# untitled.net
KiCad netlist of a schematic drawn in EAGLE
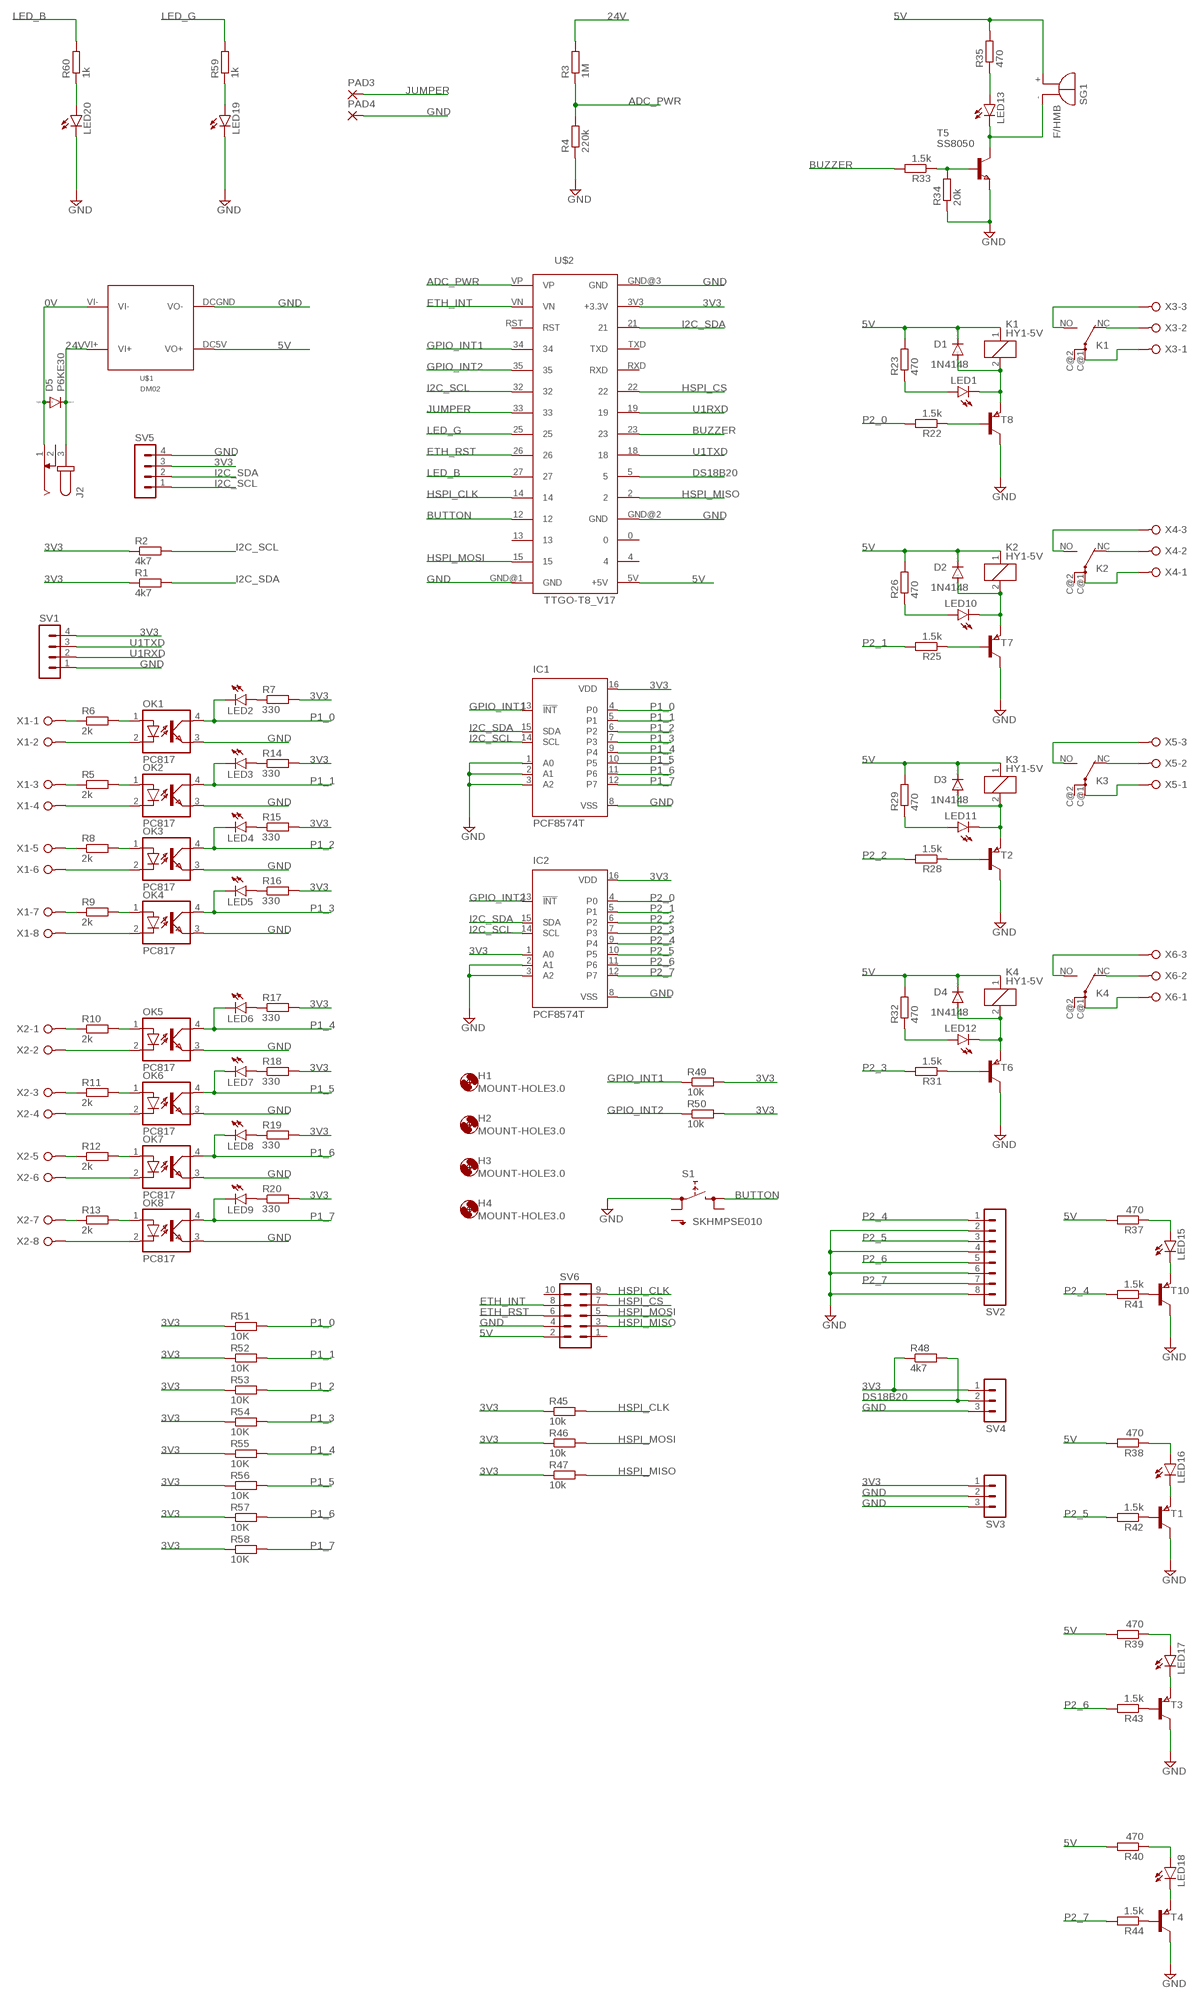
[diagram p0: schematic, sheet 1]

(export (version "E")
  (design (tool "Eeschema 10.0.6"))
  (components
    (comp (ref "D1")
      (value "1N4148")
      (footprint "eagle-import:SOD123")
      (libsource (lib "eagle-import") (part "diode_210_DIODE-SOD123"))
    )
    (comp (ref "D2")
      (value "1N4148")
      (footprint "eagle-import:SOD123")
      (libsource (lib "eagle-import") (part "diode_210_DIODE-SOD123"))
    )
    (comp (ref "D3")
      (value "1N4148")
      (footprint "eagle-import:SOD123")
      (libsource (lib "eagle-import") (part "diode_210_DIODE-SOD123"))
    )
    (comp (ref "D4")
      (value "1N4148")
      (footprint "eagle-import:SOD123")
      (libsource (lib "eagle-import") (part "diode_210_DIODE-SOD123"))
    )
    (comp (ref "D5")
      (value "P6KE30")
      (footprint "eagle-import:D-10")
      (libsource (lib "eagle-import") (part "DIODE-D-10"))
    )
    (comp (ref "H1")
      (value "MOUNT-HOLE3.0")
      (footprint "eagle-import:3,0")
      (libsource (lib "eagle-import") (part "MOUNT-HOLE3.0"))
    )
    (comp (ref "H2")
      (value "MOUNT-HOLE3.0")
      (footprint "eagle-import:3,0")
      (libsource (lib "eagle-import") (part "MOUNT-HOLE3.0"))
    )
    (comp (ref "H3")
      (value "MOUNT-HOLE3.0")
      (footprint "eagle-import:3,0")
      (libsource (lib "eagle-import") (part "MOUNT-HOLE3.0"))
    )
    (comp (ref "H4")
      (value "MOUNT-HOLE3.0")
      (footprint "eagle-import:3,0")
      (libsource (lib "eagle-import") (part "MOUNT-HOLE3.0"))
    )
    (comp (ref "IC1")
      (value "PCF8574T")
      (footprint "eagle-import:SO16W")
      (fields (field (name "MPN") "PCF8574T/3,512"))
      (libsource (lib "eagle-import") (part "PCF8574T"))
    )
    (comp (ref "IC2")
      (value "PCF8574T")
      (footprint "eagle-import:SO16W")
      (fields (field (name "MPN") "PCF8574T/3,512"))
      (libsource (lib "eagle-import") (part "PCF8574T"))
    )
    (comp (ref "J2")
      (value "JACK-PLUG0")
      (footprint "eagle-import:SPC4077")
      (libsource (lib "eagle-import") (part "JACK-PLUG0"))
    )
    (comp (ref "K1")
      (value "HY1-5V")
      (footprint "eagle-import:HY")
      (fields (field (name "MF") "AROMAT/ MATSUSHITA"))
      (libsource (lib "eagle-import") (part "HY1-5V"))
    )
    (comp (ref "K2")
      (value "HY1-5V")
      (footprint "eagle-import:HY")
      (fields (field (name "MF") "AROMAT/ MATSUSHITA"))
      (libsource (lib "eagle-import") (part "HY1-5V"))
    )
    (comp (ref "K3")
      (value "HY1-5V")
      (footprint "eagle-import:HY")
      (fields (field (name "MF") "AROMAT/ MATSUSHITA"))
      (libsource (lib "eagle-import") (part "HY1-5V"))
    )
    (comp (ref "K4")
      (value "HY1-5V")
      (footprint "eagle-import:HY")
      (fields (field (name "MF") "AROMAT/ MATSUSHITA"))
      (libsource (lib "eagle-import") (part "HY1-5V"))
    )
    (comp (ref "LED1")
      (value "LEDCHIPLED_0805")
      (footprint "eagle-import:CHIPLED_0805")
      (libsource (lib "eagle-import") (part "LEDCHIPLED_0805"))
    )
    (comp (ref "LED2")
      (value "LEDCHIPLED_0805")
      (footprint "eagle-import:CHIPLED_0805")
      (libsource (lib "eagle-import") (part "LEDCHIPLED_0805"))
    )
    (comp (ref "LED3")
      (value "LEDCHIPLED_0805")
      (footprint "eagle-import:CHIPLED_0805")
      (libsource (lib "eagle-import") (part "LEDCHIPLED_0805"))
    )
    (comp (ref "LED4")
      (value "LEDCHIPLED_0805")
      (footprint "eagle-import:CHIPLED_0805")
      (libsource (lib "eagle-import") (part "LEDCHIPLED_0805"))
    )
    (comp (ref "LED5")
      (value "LEDCHIPLED_0805")
      (footprint "eagle-import:CHIPLED_0805")
      (libsource (lib "eagle-import") (part "LEDCHIPLED_0805"))
    )
    (comp (ref "LED6")
      (value "LEDCHIPLED_0805")
      (footprint "eagle-import:CHIPLED_0805")
      (libsource (lib "eagle-import") (part "LEDCHIPLED_0805"))
    )
    (comp (ref "LED7")
      (value "LEDCHIPLED_0805")
      (footprint "eagle-import:CHIPLED_0805")
      (libsource (lib "eagle-import") (part "LEDCHIPLED_0805"))
    )
    (comp (ref "LED8")
      (value "LEDCHIPLED_0805")
      (footprint "eagle-import:CHIPLED_0805")
      (libsource (lib "eagle-import") (part "LEDCHIPLED_0805"))
    )
    (comp (ref "LED9")
      (value "LEDCHIPLED_0805")
      (footprint "eagle-import:CHIPLED_0805")
      (libsource (lib "eagle-import") (part "LEDCHIPLED_0805"))
    )
    (comp (ref "LED10")
      (value "LEDCHIPLED_0805")
      (footprint "eagle-import:CHIPLED_0805")
      (libsource (lib "eagle-import") (part "LEDCHIPLED_0805"))
    )
    (comp (ref "LED11")
      (value "LEDCHIPLED_0805")
      (footprint "eagle-import:CHIPLED_0805")
      (libsource (lib "eagle-import") (part "LEDCHIPLED_0805"))
    )
    (comp (ref "LED12")
      (value "LEDCHIPLED_0805")
      (footprint "eagle-import:CHIPLED_0805")
      (libsource (lib "eagle-import") (part "LEDCHIPLED_0805"))
    )
    (comp (ref "LED13")
      (value "LEDCHIPLED_0805")
      (footprint "eagle-import:CHIPLED_0805")
      (libsource (lib "eagle-import") (part "LEDCHIPLED_0805"))
    )
    (comp (ref "LED15")
      (value "LEDCHIPLED_0805")
      (footprint "eagle-import:CHIPLED_0805")
      (libsource (lib "eagle-import") (part "LEDCHIPLED_0805"))
    )
    (comp (ref "LED16")
      (value "LEDCHIPLED_0805")
      (footprint "eagle-import:CHIPLED_0805")
      (libsource (lib "eagle-import") (part "LEDCHIPLED_0805"))
    )
    (comp (ref "LED17")
      (value "LEDCHIPLED_0805")
      (footprint "eagle-import:CHIPLED_0805")
      (libsource (lib "eagle-import") (part "LEDCHIPLED_0805"))
    )
    (comp (ref "LED18")
      (value "LEDCHIPLED_0805")
      (footprint "eagle-import:CHIPLED_0805")
      (libsource (lib "eagle-import") (part "LEDCHIPLED_0805"))
    )
    (comp (ref "LED19")
      (value "LEDCHIPLED_0805")
      (footprint "eagle-import:CHIPLED_0805")
      (libsource (lib "eagle-import") (part "LEDCHIPLED_0805"))
    )
    (comp (ref "LED20")
      (value "LEDCHIPLED_0805")
      (footprint "eagle-import:CHIPLED_0805")
      (libsource (lib "eagle-import") (part "LEDCHIPLED_0805"))
    )
    (comp (ref "OK1")
      (value "PC817")
      (footprint "eagle-import:DIL04")
      (fields (field (name "MPN") "PC817X4J000F"))
      (libsource (lib "eagle-import") (part "PC817"))
    )
    (comp (ref "OK2")
      (value "PC817")
      (footprint "eagle-import:DIL04")
      (fields (field (name "MPN") "PC817X4J000F"))
      (libsource (lib "eagle-import") (part "PC817"))
    )
    (comp (ref "OK3")
      (value "PC817")
      (footprint "eagle-import:DIL04")
      (fields (field (name "MPN") "PC817X4J000F"))
      (libsource (lib "eagle-import") (part "PC817"))
    )
    (comp (ref "OK4")
      (value "PC817")
      (footprint "eagle-import:DIL04")
      (fields (field (name "MPN") "PC817X4J000F"))
      (libsource (lib "eagle-import") (part "PC817"))
    )
    (comp (ref "OK5")
      (value "PC817")
      (footprint "eagle-import:DIL04")
      (fields (field (name "MPN") "PC817X4J000F"))
      (libsource (lib "eagle-import") (part "PC817"))
    )
    (comp (ref "OK6")
      (value "PC817")
      (footprint "eagle-import:DIL04")
      (fields (field (name "MPN") "PC817X4J000F"))
      (libsource (lib "eagle-import") (part "PC817"))
    )
    (comp (ref "OK7")
      (value "PC817")
      (footprint "eagle-import:DIL04")
      (fields (field (name "MPN") "PC817X4J000F"))
      (libsource (lib "eagle-import") (part "PC817"))
    )
    (comp (ref "OK8")
      (value "PC817")
      (footprint "eagle-import:DIL04")
      (fields (field (name "MPN") "PC817X4J000F"))
      (libsource (lib "eagle-import") (part "PC817"))
    )
    (comp (ref "PAD3")
      (value "2,15/1,0")
      (footprint "eagle-import:2,15_1,0")
      (libsource (lib "eagle-import") (part "2,15/1,0"))
    )
    (comp (ref "PAD4")
      (value "2,15/1,0")
      (footprint "eagle-import:2,15_1,0")
      (libsource (lib "eagle-import") (part "2,15/1,0"))
    )
    (comp (ref "R1")
      (value "4k7")
      (footprint "eagle-import:R0603")
      (libsource (lib "eagle-import") (part "R-EU_R0603"))
    )
    (comp (ref "R2")
      (value "4k7")
      (footprint "eagle-import:R0603")
      (libsource (lib "eagle-import") (part "R-EU_R0603"))
    )
    (comp (ref "R3")
      (value "1M")
      (footprint "eagle-import:R0603")
      (libsource (lib "eagle-import") (part "R-EU_R0603"))
    )
    (comp (ref "R4")
      (value "220k")
      (footprint "eagle-import:R0603")
      (libsource (lib "eagle-import") (part "R-EU_R0603"))
    )
    (comp (ref "R5")
      (value "2k")
      (footprint "eagle-import:R0603")
      (libsource (lib "eagle-import") (part "R-EU_R0603"))
    )
    (comp (ref "R6")
      (value "2k")
      (footprint "eagle-import:R0603")
      (libsource (lib "eagle-import") (part "R-EU_R0603"))
    )
    (comp (ref "R7")
      (value "330")
      (footprint "eagle-import:R0603")
      (libsource (lib "eagle-import") (part "R-EU_R0603"))
    )
    (comp (ref "R8")
      (value "2k")
      (footprint "eagle-import:R0603")
      (libsource (lib "eagle-import") (part "R-EU_R0603"))
    )
    (comp (ref "R9")
      (value "2k")
      (footprint "eagle-import:R0603")
      (libsource (lib "eagle-import") (part "R-EU_R0603"))
    )
    (comp (ref "R10")
      (value "2k")
      (footprint "eagle-import:R0603")
      (libsource (lib "eagle-import") (part "R-EU_R0603"))
    )
    (comp (ref "R11")
      (value "2k")
      (footprint "eagle-import:R0603")
      (libsource (lib "eagle-import") (part "R-EU_R0603"))
    )
    (comp (ref "R12")
      (value "2k")
      (footprint "eagle-import:R0603")
      (libsource (lib "eagle-import") (part "R-EU_R0603"))
    )
    (comp (ref "R13")
      (value "2k")
      (footprint "eagle-import:R0603")
      (libsource (lib "eagle-import") (part "R-EU_R0603"))
    )
    (comp (ref "R14")
      (value "330")
      (footprint "eagle-import:R0603")
      (libsource (lib "eagle-import") (part "R-EU_R0603"))
    )
    (comp (ref "R15")
      (value "330")
      (footprint "eagle-import:R0603")
      (libsource (lib "eagle-import") (part "R-EU_R0603"))
    )
    (comp (ref "R16")
      (value "330")
      (footprint "eagle-import:R0603")
      (libsource (lib "eagle-import") (part "R-EU_R0603"))
    )
    (comp (ref "R17")
      (value "330")
      (footprint "eagle-import:R0603")
      (libsource (lib "eagle-import") (part "R-EU_R0603"))
    )
    (comp (ref "R18")
      (value "330")
      (footprint "eagle-import:R0603")
      (libsource (lib "eagle-import") (part "R-EU_R0603"))
    )
    (comp (ref "R19")
      (value "330")
      (footprint "eagle-import:R0603")
      (libsource (lib "eagle-import") (part "R-EU_R0603"))
    )
    (comp (ref "R20")
      (value "330")
      (footprint "eagle-import:R0603")
      (libsource (lib "eagle-import") (part "R-EU_R0603"))
    )
    (comp (ref "R22")
      (value "1.5k")
      (footprint "eagle-import:R0603")
      (libsource (lib "eagle-import") (part "R-EU_R0603"))
    )
    (comp (ref "R23")
      (value "470")
      (footprint "eagle-import:R0603")
      (libsource (lib "eagle-import") (part "R-EU_R0603"))
    )
    (comp (ref "R25")
      (value "1.5k")
      (footprint "eagle-import:R0603")
      (libsource (lib "eagle-import") (part "R-EU_R0603"))
    )
    (comp (ref "R26")
      (value "470")
      (footprint "eagle-import:R0603")
      (libsource (lib "eagle-import") (part "R-EU_R0603"))
    )
    (comp (ref "R28")
      (value "1.5k")
      (footprint "eagle-import:R0603")
      (libsource (lib "eagle-import") (part "R-EU_R0603"))
    )
    (comp (ref "R29")
      (value "470")
      (footprint "eagle-import:R0603")
      (libsource (lib "eagle-import") (part "R-EU_R0603"))
    )
    (comp (ref "R31")
      (value "1.5k")
      (footprint "eagle-import:R0603")
      (libsource (lib "eagle-import") (part "R-EU_R0603"))
    )
    (comp (ref "R32")
      (value "470")
      (footprint "eagle-import:R0603")
      (libsource (lib "eagle-import") (part "R-EU_R0603"))
    )
    (comp (ref "R33")
      (value "1.5k")
      (footprint "eagle-import:R0603")
      (libsource (lib "eagle-import") (part "R-EU_R0603"))
    )
    (comp (ref "R34")
      (value "20k")
      (footprint "eagle-import:R0603")
      (libsource (lib "eagle-import") (part "R-EU_R0603"))
    )
    (comp (ref "R35")
      (value "470")
      (footprint "eagle-import:R0603")
      (libsource (lib "eagle-import") (part "R-EU_R0603"))
    )
    (comp (ref "R37")
      (value "470")
      (footprint "eagle-import:R0603")
      (libsource (lib "eagle-import") (part "R-EU_R0603"))
    )
    (comp (ref "R38")
      (value "470")
      (footprint "eagle-import:R0603")
      (libsource (lib "eagle-import") (part "R-EU_R0603"))
    )
    (comp (ref "R39")
      (value "470")
      (footprint "eagle-import:R0603")
      (libsource (lib "eagle-import") (part "R-EU_R0603"))
    )
    (comp (ref "R40")
      (value "470")
      (footprint "eagle-import:R0603")
      (libsource (lib "eagle-import") (part "R-EU_R0603"))
    )
    (comp (ref "R41")
      (value "1.5k")
      (footprint "eagle-import:R0603")
      (libsource (lib "eagle-import") (part "R-EU_R0603"))
    )
    (comp (ref "R42")
      (value "1.5k")
      (footprint "eagle-import:R0603")
      (libsource (lib "eagle-import") (part "R-EU_R0603"))
    )
    (comp (ref "R43")
      (value "1.5k")
      (footprint "eagle-import:R0603")
      (libsource (lib "eagle-import") (part "R-EU_R0603"))
    )
    (comp (ref "R44")
      (value "1.5k")
      (footprint "eagle-import:R0603")
      (libsource (lib "eagle-import") (part "R-EU_R0603"))
    )
    (comp (ref "R45")
      (value "10k")
      (footprint "eagle-import:R0603")
      (libsource (lib "eagle-import") (part "R-EU_R0603"))
    )
    (comp (ref "R46")
      (value "10k")
      (footprint "eagle-import:R0603")
      (libsource (lib "eagle-import") (part "R-EU_R0603"))
    )
    (comp (ref "R47")
      (value "10k")
      (footprint "eagle-import:R0603")
      (libsource (lib "eagle-import") (part "R-EU_R0603"))
    )
    (comp (ref "R48")
      (value "4k7")
      (footprint "eagle-import:R0603")
      (libsource (lib "eagle-import") (part "R-EU_R0603"))
    )
    (comp (ref "R49")
      (value "10k")
      (footprint "eagle-import:R0603")
      (libsource (lib "eagle-import") (part "R-EU_R0603"))
    )
    (comp (ref "R50")
      (value "10k")
      (footprint "eagle-import:R0603")
      (libsource (lib "eagle-import") (part "R-EU_R0603"))
    )
    (comp (ref "R51")
      (value "10K")
      (footprint "eagle-import:R0603")
      (libsource (lib "eagle-import") (part "R-EU_R0603"))
    )
    (comp (ref "R52")
      (value "10K")
      (footprint "eagle-import:R0603")
      (libsource (lib "eagle-import") (part "R-EU_R0603"))
    )
    (comp (ref "R53")
      (value "10K")
      (footprint "eagle-import:R0603")
      (libsource (lib "eagle-import") (part "R-EU_R0603"))
    )
    (comp (ref "R54")
      (value "10K")
      (footprint "eagle-import:R0603")
      (libsource (lib "eagle-import") (part "R-EU_R0603"))
    )
    (comp (ref "R55")
      (value "10K")
      (footprint "eagle-import:R0603")
      (libsource (lib "eagle-import") (part "R-EU_R0603"))
    )
    (comp (ref "R56")
      (value "10K")
      (footprint "eagle-import:R0603")
      (libsource (lib "eagle-import") (part "R-EU_R0603"))
    )
    (comp (ref "R57")
      (value "10K")
      (footprint "eagle-import:R0603")
      (libsource (lib "eagle-import") (part "R-EU_R0603"))
    )
    (comp (ref "R58")
      (value "10K")
      (footprint "eagle-import:R0603")
      (libsource (lib "eagle-import") (part "R-EU_R0603"))
    )
    (comp (ref "R59")
      (value "1k")
      (footprint "eagle-import:R0603")
      (libsource (lib "eagle-import") (part "R-EU_R0603"))
    )
    (comp (ref "R60")
      (value "1k")
      (footprint "eagle-import:R0603")
      (libsource (lib "eagle-import") (part "R-EU_R0603"))
    )
    (comp (ref "S1")
      (value "SKHMPSE010")
      (footprint "eagle-import:SKHMPXE010")
      (libsource (lib "eagle-import") (part "SKHMPE010S"))
    )
    (comp (ref "SG1")
      (value "F/HMB")
      (footprint "eagle-import:F_HMB")
      (libsource (lib "eagle-import") (part "F/HMB"))
    )
    (comp (ref "SV1")
      (value "MA04-1")
      (footprint "eagle-import:MA04-1")
      (libsource (lib "eagle-import") (part "MA04-1"))
    )
    (comp (ref "SV2")
      (value "MA08-1")
      (footprint "eagle-import:MA08-1")
      (libsource (lib "eagle-import") (part "MA08-1"))
    )
    (comp (ref "SV3")
      (value "MA03-1")
      (footprint "eagle-import:MA03-1")
      (libsource (lib "eagle-import") (part "MA03-1"))
    )
    (comp (ref "SV4")
      (value "MA03-1")
      (footprint "eagle-import:MA03-1")
      (libsource (lib "eagle-import") (part "MA03-1"))
    )
    (comp (ref "SV5")
      (value "MA04-1")
      (footprint "eagle-import:MA04-1")
      (libsource (lib "eagle-import") (part "MA04-1"))
    )
    (comp (ref "SV6")
      (value "MA05-2")
      (footprint "eagle-import:MA05-2")
      (libsource (lib "eagle-import") (part "MA05-2"))
    )
    (comp (ref "T1")
      (value "PNPSOT23")
      (footprint "eagle-import:SOT-23")
      (fields (field (name "MPN") "DSS20200L-7"))
      (libsource (lib "eagle-import") (part "PNPSOT23"))
    )
    (comp (ref "T2")
      (value "PNPSOT23")
      (footprint "eagle-import:SOT-23")
      (fields (field (name "MPN") "DSS20200L-7"))
      (libsource (lib "eagle-import") (part "PNPSOT23"))
    )
    (comp (ref "T3")
      (value "PNPSOT23")
      (footprint "eagle-import:SOT-23")
      (fields (field (name "MPN") "DSS20200L-7"))
      (libsource (lib "eagle-import") (part "PNPSOT23"))
    )
    (comp (ref "T4")
      (value "PNPSOT23")
      (footprint "eagle-import:SOT-23")
      (fields (field (name "MPN") "DSS20200L-7"))
      (libsource (lib "eagle-import") (part "PNPSOT23"))
    )
    (comp (ref "T5")
      (value "SS8050")
      (footprint "eagle-import:SOT-23")
      (fields (field (name "MPN") "DSS20201L-7"))
      (libsource (lib "eagle-import") (part "NPNSOT23"))
    )
    (comp (ref "T6")
      (value "PNPSOT23")
      (footprint "eagle-import:SOT-23")
      (fields (field (name "MPN") "DSS20200L-7"))
      (libsource (lib "eagle-import") (part "PNPSOT23"))
    )
    (comp (ref "T7")
      (value "PNPSOT23")
      (footprint "eagle-import:SOT-23")
      (fields (field (name "MPN") "DSS20200L-7"))
      (libsource (lib "eagle-import") (part "PNPSOT23"))
    )
    (comp (ref "T8")
      (value "PNPSOT23")
      (footprint "eagle-import:SOT-23")
      (fields (field (name "MPN") "DSS20200L-7"))
      (libsource (lib "eagle-import") (part "PNPSOT23"))
    )
    (comp (ref "T10")
      (value "PNPSOT23")
      (footprint "eagle-import:SOT-23")
      (fields (field (name "MPN") "DSS20200L-7"))
      (libsource (lib "eagle-import") (part "PNPSOT23"))
    )
    (comp (ref "U$1")
      (value "DM02")
      (footprint "eagle-import:DM02")
      (libsource (lib "eagle-import") (part "DM02"))
    )
    (comp (ref "U$2")
      (value "TTGO-T8_V17")
      (footprint "eagle-import:TTGO-T8_V17")
      (libsource (lib "eagle-import") (part "TTGO-T8_V17"))
    )
    (comp (ref "X1")
      (value "W237-08P")
      (footprint "eagle-import:W237-8P")
      (libsource (lib "eagle-import") (part "W237-08P"))
    )
    (comp (ref "X2")
      (value "W237-08P")
      (footprint "eagle-import:W237-8P")
      (libsource (lib "eagle-import") (part "W237-08P"))
    )
    (comp (ref "X3")
      (value "W237-03P")
      (footprint "eagle-import:W237-133")
      (libsource (lib "eagle-import") (part "W237-03P"))
    )
    (comp (ref "X4")
      (value "W237-03P")
      (footprint "eagle-import:W237-133")
      (libsource (lib "eagle-import") (part "W237-03P"))
    )
    (comp (ref "X5")
      (value "W237-03P")
      (footprint "eagle-import:W237-133")
      (libsource (lib "eagle-import") (part "W237-03P"))
    )
    (comp (ref "X6")
      (value "W237-03P")
      (footprint "eagle-import:W237-133")
      (libsource (lib "eagle-import") (part "W237-03P"))
    )
  )
  (nets
    (net (code "1") (name "/0V") (class "Default")
      (node (ref "D5") (pin "A") (pinfunction "A_A") (pintype "passive"))
      (node (ref "J2") (pin "1") (pinfunction "1_1") (pintype "passive"))
      (node (ref "U$1") (pin "VI-") (pinfunction "VI-_VI-") (pintype "bidirectional"))
    )
    (net (code "2") (name "/3V3") (class "Default")
      (node (ref "IC1") (pin "16") (pinfunction "VDD_16") (pintype "power_in"))
      (node (ref "IC2") (pin "1") (pinfunction "A0_1") (pintype "input"))
      (node (ref "IC2") (pin "16") (pinfunction "VDD_16") (pintype "power_in"))
      (node (ref "R1") (pin "1") (pinfunction "1_1") (pintype "passive"))
      (node (ref "R14") (pin "2") (pinfunction "2_2") (pintype "passive"))
      (node (ref "R15") (pin "2") (pinfunction "2_2") (pintype "passive"))
      (node (ref "R16") (pin "2") (pinfunction "2_2") (pintype "passive"))
      (node (ref "R17") (pin "2") (pinfunction "2_2") (pintype "passive"))
      (node (ref "R18") (pin "2") (pinfunction "2_2") (pintype "passive"))
      (node (ref "R19") (pin "2") (pinfunction "2_2") (pintype "passive"))
      (node (ref "R2") (pin "1") (pinfunction "1_1") (pintype "passive"))
      (node (ref "R20") (pin "2") (pinfunction "2_2") (pintype "passive"))
      (node (ref "R45") (pin "1") (pinfunction "1_1") (pintype "passive"))
      (node (ref "R46") (pin "1") (pinfunction "1_1") (pintype "passive"))
      (node (ref "R47") (pin "1") (pinfunction "1_1") (pintype "passive"))
      (node (ref "R48") (pin "1") (pinfunction "1_1") (pintype "passive"))
      (node (ref "R49") (pin "2") (pinfunction "2_2") (pintype "passive"))
      (node (ref "R50") (pin "2") (pinfunction "2_2") (pintype "passive"))
      (node (ref "R51") (pin "1") (pinfunction "1_1") (pintype "passive"))
      (node (ref "R52") (pin "1") (pinfunction "1_1") (pintype "passive"))
      (node (ref "R53") (pin "1") (pinfunction "1_1") (pintype "passive"))
      (node (ref "R54") (pin "1") (pinfunction "1_1") (pintype "passive"))
      (node (ref "R55") (pin "1") (pinfunction "1_1") (pintype "passive"))
      (node (ref "R56") (pin "1") (pinfunction "1_1") (pintype "passive"))
      (node (ref "R57") (pin "1") (pinfunction "1_1") (pintype "passive"))
      (node (ref "R58") (pin "1") (pinfunction "1_1") (pintype "passive"))
      (node (ref "R7") (pin "2") (pinfunction "2_2") (pintype "passive"))
      (node (ref "SV1") (pin "4") (pinfunction "4_4") (pintype "passive"))
      (node (ref "SV3") (pin "1") (pinfunction "1_1") (pintype "passive"))
      (node (ref "SV4") (pin "1") (pinfunction "1_1") (pintype "passive"))
      (node (ref "SV5") (pin "3") (pinfunction "3_3") (pintype "passive"))
      (node (ref "U$2") (pin "3V3") (pinfunction "+3.3V_3V3") (pintype "bidirectional"))
    )
    (net (code "3") (name "/5V") (class "Default")
      (node (ref "D1") (pin "C") (pinfunction "C_C") (pintype "passive"))
      (node (ref "D2") (pin "C") (pinfunction "C_C") (pintype "passive"))
      (node (ref "D3") (pin "C") (pinfunction "C_C") (pintype "passive"))
      (node (ref "D4") (pin "C") (pinfunction "C_C") (pintype "passive"))
      (node (ref "K1") (pin "1") (pinfunction "1_1") (pintype "passive"))
      (node (ref "K2") (pin "1") (pinfunction "1_1") (pintype "passive"))
      (node (ref "K3") (pin "1") (pinfunction "1_1") (pintype "passive"))
      (node (ref "K4") (pin "1") (pinfunction "1_1") (pintype "passive"))
      (node (ref "R23") (pin "2") (pinfunction "2_2") (pintype "passive"))
      (node (ref "R26") (pin "2") (pinfunction "2_2") (pintype "passive"))
      (node (ref "R29") (pin "2") (pinfunction "2_2") (pintype "passive"))
      (node (ref "R32") (pin "2") (pinfunction "2_2") (pintype "passive"))
      (node (ref "R35") (pin "2") (pinfunction "2_2") (pintype "passive"))
      (node (ref "R37") (pin "2") (pinfunction "2_2") (pintype "passive"))
      (node (ref "R38") (pin "2") (pinfunction "2_2") (pintype "passive"))
      (node (ref "R39") (pin "2") (pinfunction "2_2") (pintype "passive"))
      (node (ref "R40") (pin "2") (pinfunction "2_2") (pintype "passive"))
      (node (ref "SG1") (pin "+") (pinfunction "+_+") (pintype "passive"))
      (node (ref "SV6") (pin "2") (pinfunction "2_2") (pintype "passive"))
      (node (ref "U$1") (pin "DC5V") (pinfunction "VO+_DC5V") (pintype "bidirectional"))
      (node (ref "U$2") (pin "5V") (pinfunction "+5V_5V") (pintype "bidirectional"))
    )
    (net (code "4") (name "/24V") (class "Default")
      (node (ref "D5") (pin "C") (pinfunction "C_C") (pintype "passive"))
      (node (ref "J2") (pin "3") (pinfunction "3_3") (pintype "passive"))
      (node (ref "R3") (pin "2") (pinfunction "2_2") (pintype "passive"))
      (node (ref "U$1") (pin "VI+") (pinfunction "VI+_VI+") (pintype "bidirectional"))
    )
    (net (code "5") (name "/ADC_PWR") (class "Default")
      (node (ref "R3") (pin "1") (pinfunction "1_1") (pintype "passive"))
      (node (ref "R4") (pin "2") (pinfunction "2_2") (pintype "passive"))
      (node (ref "U$2") (pin "VP") (pinfunction "VP_VP") (pintype "bidirectional"))
    )
    (net (code "6") (name "/BUTTON") (class "Default")
      (node (ref "S1") (pin "3") (pinfunction "2.1_3") (pintype "passive"))
      (node (ref "U$2") (pin "12") (pinfunction "12_12") (pintype "bidirectional"))
    )
    (net (code "7") (name "/BUZZER") (class "Default")
      (node (ref "R33") (pin "2") (pinfunction "2_2") (pintype "passive"))
      (node (ref "U$2") (pin "23") (pinfunction "23_23") (pintype "bidirectional"))
    )
    (net (code "8") (name "/DS18B20") (class "Default")
      (node (ref "R48") (pin "2") (pinfunction "2_2") (pintype "passive"))
      (node (ref "SV4") (pin "2") (pinfunction "2_2") (pintype "passive"))
      (node (ref "U$2") (pin "5") (pinfunction "5_5") (pintype "bidirectional"))
    )
    (net (code "9") (name "/ETH_INT") (class "Default")
      (node (ref "SV6") (pin "8") (pinfunction "8_8") (pintype "passive"))
      (node (ref "U$2") (pin "VN") (pinfunction "VN_VN") (pintype "bidirectional"))
    )
    (net (code "10") (name "/ETH_RST") (class "Default")
      (node (ref "SV6") (pin "6") (pinfunction "6_6") (pintype "passive"))
      (node (ref "U$2") (pin "26") (pinfunction "26_26") (pintype "bidirectional"))
    )
    (net (code "11") (name "/GPIO_INT1") (class "Default")
      (node (ref "IC1") (pin "13") (pinfunction "~{INT}_13") (pintype "output"))
      (node (ref "R49") (pin "1") (pinfunction "1_1") (pintype "passive"))
      (node (ref "U$2") (pin "34") (pinfunction "34_34") (pintype "bidirectional"))
    )
    (net (code "12") (name "/GPIO_INT2") (class "Default")
      (node (ref "IC2") (pin "13") (pinfunction "~{INT}_13") (pintype "output"))
      (node (ref "R50") (pin "1") (pinfunction "1_1") (pintype "passive"))
      (node (ref "U$2") (pin "35") (pinfunction "35_35") (pintype "bidirectional"))
    )
    (net (code "13") (name "/HSPI_CLK") (class "Default")
      (node (ref "R45") (pin "2") (pinfunction "2_2") (pintype "passive"))
      (node (ref "SV6") (pin "9") (pinfunction "9_9") (pintype "passive"))
      (node (ref "U$2") (pin "14") (pinfunction "14_14") (pintype "bidirectional"))
    )
    (net (code "14") (name "/HSPI_CS") (class "Default")
      (node (ref "SV6") (pin "7") (pinfunction "7_7") (pintype "passive"))
      (node (ref "U$2") (pin "22") (pinfunction "22_22") (pintype "bidirectional"))
    )
    (net (code "15") (name "/HSPI_MISO") (class "Default")
      (node (ref "R47") (pin "2") (pinfunction "2_2") (pintype "passive"))
      (node (ref "SV6") (pin "3") (pinfunction "3_3") (pintype "passive"))
      (node (ref "U$2") (pin "2") (pinfunction "2_2") (pintype "bidirectional"))
    )
    (net (code "16") (name "/HSPI_MOSI") (class "Default")
      (node (ref "R46") (pin "2") (pinfunction "2_2") (pintype "passive"))
      (node (ref "SV6") (pin "5") (pinfunction "5_5") (pintype "passive"))
      (node (ref "U$2") (pin "15") (pinfunction "15_15") (pintype "bidirectional"))
    )
    (net (code "17") (name "/I2C_SCL") (class "Default")
      (node (ref "IC1") (pin "14") (pinfunction "SCL_14") (pintype "input"))
      (node (ref "IC2") (pin "14") (pinfunction "SCL_14") (pintype "input"))
      (node (ref "R2") (pin "2") (pinfunction "2_2") (pintype "passive"))
      (node (ref "SV5") (pin "1") (pinfunction "1_1") (pintype "passive"))
      (node (ref "U$2") (pin "32") (pinfunction "32_32") (pintype "bidirectional"))
    )
    (net (code "18") (name "/I2C_SDA") (class "Default")
      (node (ref "IC1") (pin "15") (pinfunction "SDA_15") (pintype "bidirectional"))
      (node (ref "IC2") (pin "15") (pinfunction "SDA_15") (pintype "bidirectional"))
      (node (ref "R1") (pin "2") (pinfunction "2_2") (pintype "passive"))
      (node (ref "SV5") (pin "2") (pinfunction "2_2") (pintype "passive"))
      (node (ref "U$2") (pin "21") (pinfunction "21_21") (pintype "bidirectional"))
    )
    (net (code "19") (name "/JUMPER") (class "Default")
      (node (ref "PAD3") (pin "1") (pinfunction "P_1") (pintype "passive"))
      (node (ref "U$2") (pin "33") (pinfunction "33_33") (pintype "bidirectional"))
    )
    (net (code "20") (name "/LED_B") (class "Default")
      (node (ref "R60") (pin "2") (pinfunction "2_2") (pintype "passive"))
      (node (ref "U$2") (pin "27") (pinfunction "27_27") (pintype "bidirectional"))
    )
    (net (code "21") (name "/LED_G") (class "Default")
      (node (ref "R59") (pin "2") (pinfunction "2_2") (pintype "passive"))
      (node (ref "U$2") (pin "25") (pinfunction "25_25") (pintype "bidirectional"))
    )
    (net (code "22") (name "/P1_0") (class "Default")
      (node (ref "IC1") (pin "4") (pinfunction "P0_4") (pintype "bidirectional"))
      (node (ref "LED2") (pin "C") (pinfunction "C_C") (pintype "passive"))
      (node (ref "OK1") (pin "4") (pinfunction "COL_4") (pintype "passive"))
      (node (ref "R51") (pin "2") (pinfunction "2_2") (pintype "passive"))
    )
    (net (code "23") (name "/P1_1") (class "Default")
      (node (ref "IC1") (pin "5") (pinfunction "P1_5") (pintype "bidirectional"))
      (node (ref "LED3") (pin "C") (pinfunction "C_C") (pintype "passive"))
      (node (ref "OK2") (pin "4") (pinfunction "COL_4") (pintype "passive"))
      (node (ref "R52") (pin "2") (pinfunction "2_2") (pintype "passive"))
    )
    (net (code "24") (name "/P1_2") (class "Default")
      (node (ref "IC1") (pin "6") (pinfunction "P2_6") (pintype "bidirectional"))
      (node (ref "LED4") (pin "C") (pinfunction "C_C") (pintype "passive"))
      (node (ref "OK3") (pin "4") (pinfunction "COL_4") (pintype "passive"))
      (node (ref "R53") (pin "2") (pinfunction "2_2") (pintype "passive"))
    )
    (net (code "25") (name "/P1_3") (class "Default")
      (node (ref "IC1") (pin "7") (pinfunction "P3_7") (pintype "bidirectional"))
      (node (ref "LED5") (pin "C") (pinfunction "C_C") (pintype "passive"))
      (node (ref "OK4") (pin "4") (pinfunction "COL_4") (pintype "passive"))
      (node (ref "R54") (pin "2") (pinfunction "2_2") (pintype "passive"))
    )
    (net (code "26") (name "/P1_4") (class "Default")
      (node (ref "IC1") (pin "9") (pinfunction "P4_9") (pintype "bidirectional"))
      (node (ref "LED6") (pin "C") (pinfunction "C_C") (pintype "passive"))
      (node (ref "OK5") (pin "4") (pinfunction "COL_4") (pintype "passive"))
      (node (ref "R55") (pin "2") (pinfunction "2_2") (pintype "passive"))
    )
    (net (code "27") (name "/P1_5") (class "Default")
      (node (ref "IC1") (pin "10") (pinfunction "P5_10") (pintype "bidirectional"))
      (node (ref "LED7") (pin "C") (pinfunction "C_C") (pintype "passive"))
      (node (ref "OK6") (pin "4") (pinfunction "COL_4") (pintype "passive"))
      (node (ref "R56") (pin "2") (pinfunction "2_2") (pintype "passive"))
    )
    (net (code "28") (name "/P1_6") (class "Default")
      (node (ref "IC1") (pin "11") (pinfunction "P6_11") (pintype "bidirectional"))
      (node (ref "LED8") (pin "C") (pinfunction "C_C") (pintype "passive"))
      (node (ref "OK7") (pin "4") (pinfunction "COL_4") (pintype "passive"))
      (node (ref "R57") (pin "2") (pinfunction "2_2") (pintype "passive"))
    )
    (net (code "29") (name "/P1_7") (class "Default")
      (node (ref "IC1") (pin "12") (pinfunction "P7_12") (pintype "bidirectional"))
      (node (ref "LED9") (pin "C") (pinfunction "C_C") (pintype "passive"))
      (node (ref "OK8") (pin "4") (pinfunction "COL_4") (pintype "passive"))
      (node (ref "R58") (pin "2") (pinfunction "2_2") (pintype "passive"))
    )
    (net (code "30") (name "/P2_0") (class "Default")
      (node (ref "IC2") (pin "4") (pinfunction "P0_4") (pintype "bidirectional"))
      (node (ref "R22") (pin "2") (pinfunction "2_2") (pintype "passive"))
    )
    (net (code "31") (name "/P2_1") (class "Default")
      (node (ref "IC2") (pin "5") (pinfunction "P1_5") (pintype "bidirectional"))
      (node (ref "R25") (pin "2") (pinfunction "2_2") (pintype "passive"))
    )
    (net (code "32") (name "/P2_2") (class "Default")
      (node (ref "IC2") (pin "6") (pinfunction "P2_6") (pintype "bidirectional"))
      (node (ref "R28") (pin "2") (pinfunction "2_2") (pintype "passive"))
    )
    (net (code "33") (name "/P2_3") (class "Default")
      (node (ref "IC2") (pin "7") (pinfunction "P3_7") (pintype "bidirectional"))
      (node (ref "R31") (pin "2") (pinfunction "2_2") (pintype "passive"))
    )
    (net (code "34") (name "/P2_4") (class "Default")
      (node (ref "IC2") (pin "9") (pinfunction "P4_9") (pintype "bidirectional"))
      (node (ref "R41") (pin "2") (pinfunction "2_2") (pintype "passive"))
      (node (ref "SV2") (pin "1") (pinfunction "1_1") (pintype "passive"))
    )
    (net (code "35") (name "/P2_5") (class "Default")
      (node (ref "IC2") (pin "10") (pinfunction "P5_10") (pintype "bidirectional"))
      (node (ref "R42") (pin "2") (pinfunction "2_2") (pintype "passive"))
      (node (ref "SV2") (pin "3") (pinfunction "3_3") (pintype "passive"))
    )
    (net (code "36") (name "/P2_6") (class "Default")
      (node (ref "IC2") (pin "11") (pinfunction "P6_11") (pintype "bidirectional"))
      (node (ref "R43") (pin "2") (pinfunction "2_2") (pintype "passive"))
      (node (ref "SV2") (pin "5") (pinfunction "5_5") (pintype "passive"))
    )
    (net (code "37") (name "/P2_7") (class "Default")
      (node (ref "IC2") (pin "12") (pinfunction "P7_12") (pintype "bidirectional"))
      (node (ref "R44") (pin "2") (pinfunction "2_2") (pintype "passive"))
      (node (ref "SV2") (pin "7") (pinfunction "7_7") (pintype "passive"))
    )
    (net (code "38") (name "/U1RXD") (class "Default")
      (node (ref "SV1") (pin "2") (pinfunction "2_2") (pintype "passive"))
      (node (ref "U$2") (pin "19") (pinfunction "19_19") (pintype "bidirectional"))
    )
    (net (code "39") (name "/U1TXD") (class "Default")
      (node (ref "SV1") (pin "3") (pinfunction "3_3") (pintype "passive"))
      (node (ref "U$2") (pin "18") (pinfunction "18_18") (pintype "bidirectional"))
    )
    (net (code "40") (name "GND") (class "Default")
      (node (ref "IC1") (pin "1") (pinfunction "A0_1") (pintype "input"))
      (node (ref "IC1") (pin "2") (pinfunction "A1_2") (pintype "input"))
      (node (ref "IC1") (pin "3") (pinfunction "A2_3") (pintype "input"))
      (node (ref "IC1") (pin "8") (pinfunction "VSS_8") (pintype "power_in"))
      (node (ref "IC2") (pin "2") (pinfunction "A1_2") (pintype "input"))
      (node (ref "IC2") (pin "3") (pinfunction "A2_3") (pintype "input"))
      (node (ref "IC2") (pin "8") (pinfunction "VSS_8") (pintype "power_in"))
      (node (ref "LED19") (pin "C") (pinfunction "C_C") (pintype "passive"))
      (node (ref "LED20") (pin "C") (pinfunction "C_C") (pintype "passive"))
      (node (ref "OK1") (pin "3") (pinfunction "EMIT_3") (pintype "passive"))
      (node (ref "OK2") (pin "3") (pinfunction "EMIT_3") (pintype "passive"))
      (node (ref "OK3") (pin "3") (pinfunction "EMIT_3") (pintype "passive"))
      (node (ref "OK4") (pin "3") (pinfunction "EMIT_3") (pintype "passive"))
      (node (ref "OK5") (pin "3") (pinfunction "EMIT_3") (pintype "passive"))
      (node (ref "OK6") (pin "3") (pinfunction "EMIT_3") (pintype "passive"))
      (node (ref "OK7") (pin "3") (pinfunction "EMIT_3") (pintype "passive"))
      (node (ref "OK8") (pin "3") (pinfunction "EMIT_3") (pintype "passive"))
      (node (ref "PAD4") (pin "1") (pinfunction "P_1") (pintype "passive"))
      (node (ref "R34") (pin "1") (pinfunction "1_1") (pintype "passive"))
      (node (ref "R4") (pin "1") (pinfunction "1_1") (pintype "passive"))
      (node (ref "S1") (pin "1") (pinfunction "1.1_1") (pintype "passive"))
      (node (ref "SV1") (pin "1") (pinfunction "1_1") (pintype "passive"))
      (node (ref "SV2") (pin "2") (pinfunction "2_2") (pintype "passive"))
      (node (ref "SV2") (pin "4") (pinfunction "4_4") (pintype "passive"))
      (node (ref "SV2") (pin "6") (pinfunction "6_6") (pintype "passive"))
      (node (ref "SV2") (pin "8") (pinfunction "8_8") (pintype "passive"))
      (node (ref "SV3") (pin "2") (pinfunction "2_2") (pintype "passive"))
      (node (ref "SV3") (pin "3") (pinfunction "3_3") (pintype "passive"))
      (node (ref "SV4") (pin "3") (pinfunction "3_3") (pintype "passive"))
      (node (ref "SV5") (pin "4") (pinfunction "4_4") (pintype "passive"))
      (node (ref "SV6") (pin "4") (pinfunction "4_4") (pintype "passive"))
      (node (ref "T1") (pin "1") (pinfunction "C_1") (pintype "passive"))
      (node (ref "T10") (pin "1") (pinfunction "C_1") (pintype "passive"))
      (node (ref "T2") (pin "1") (pinfunction "C_1") (pintype "passive"))
      (node (ref "T3") (pin "1") (pinfunction "C_1") (pintype "passive"))
      (node (ref "T4") (pin "1") (pinfunction "C_1") (pintype "passive"))
      (node (ref "T5") (pin "2") (pinfunction "E_2") (pintype "passive"))
      (node (ref "T6") (pin "1") (pinfunction "C_1") (pintype "passive"))
      (node (ref "T7") (pin "1") (pinfunction "C_1") (pintype "passive"))
      (node (ref "T8") (pin "1") (pinfunction "C_1") (pintype "passive"))
      (node (ref "U$1") (pin "DCGND") (pinfunction "VO-_DCGND") (pintype "bidirectional"))
      (node (ref "U$2") (pin "GND@1") (pinfunction "GND_GND@1") (pintype "bidirectional"))
      (node (ref "U$2") (pin "GND@2") (pinfunction "GND_GND@2") (pintype "bidirectional"))
      (node (ref "U$2") (pin "GND@3") (pinfunction "GND_GND@3") (pintype "bidirectional"))
    )
    (net (code "41") (name "Net-(K1B-O)") (class "Default")
      (node (ref "K1") (pin "NC") (pinfunction "O_NC") (pintype "passive"))
      (node (ref "X3") (pin "2") (pinfunction "KL_2") (pintype "passive"))
    )
    (net (code "42") (name "Net-(K1B-S)") (class "Default")
      (node (ref "K1") (pin "NO") (pinfunction "S_NO") (pintype "passive"))
      (node (ref "X3") (pin "3") (pinfunction "KL_3") (pintype "passive"))
    )
    (net (code "43") (name "Net-(K2B-O)") (class "Default")
      (node (ref "K2") (pin "NC") (pinfunction "O_NC") (pintype "passive"))
      (node (ref "X4") (pin "2") (pinfunction "KL_2") (pintype "passive"))
    )
    (net (code "44") (name "Net-(K2B-S)") (class "Default")
      (node (ref "K2") (pin "NO") (pinfunction "S_NO") (pintype "passive"))
      (node (ref "X4") (pin "3") (pinfunction "KL_3") (pintype "passive"))
    )
    (net (code "45") (name "Net-(K3B-O)") (class "Default")
      (node (ref "K3") (pin "NC") (pinfunction "O_NC") (pintype "passive"))
      (node (ref "X5") (pin "2") (pinfunction "KL_2") (pintype "passive"))
    )
    (net (code "46") (name "Net-(K3B-S)") (class "Default")
      (node (ref "K3") (pin "NO") (pinfunction "S_NO") (pintype "passive"))
      (node (ref "X5") (pin "3") (pinfunction "KL_3") (pintype "passive"))
    )
    (net (code "47") (name "Net-(K4B-O)") (class "Default")
      (node (ref "K4") (pin "NC") (pinfunction "O_NC") (pintype "passive"))
      (node (ref "X6") (pin "2") (pinfunction "KL_2") (pintype "passive"))
    )
    (net (code "48") (name "Net-(K4B-S)") (class "Default")
      (node (ref "K4") (pin "NO") (pinfunction "S_NO") (pintype "passive"))
      (node (ref "X6") (pin "3") (pinfunction "KL_3") (pintype "passive"))
    )
    (net (code "49") (name "Net-(LED1-PadA)") (class "Default")
      (node (ref "LED1") (pin "A") (pinfunction "A_A") (pintype "passive"))
      (node (ref "R23") (pin "1") (pinfunction "1_1") (pintype "passive"))
    )
    (net (code "50") (name "Net-(LED2-PadA)") (class "Default")
      (node (ref "LED2") (pin "A") (pinfunction "A_A") (pintype "passive"))
      (node (ref "R7") (pin "1") (pinfunction "1_1") (pintype "passive"))
    )
    (net (code "51") (name "Net-(LED3-PadA)") (class "Default")
      (node (ref "LED3") (pin "A") (pinfunction "A_A") (pintype "passive"))
      (node (ref "R14") (pin "1") (pinfunction "1_1") (pintype "passive"))
    )
    (net (code "52") (name "Net-(LED4-PadA)") (class "Default")
      (node (ref "LED4") (pin "A") (pinfunction "A_A") (pintype "passive"))
      (node (ref "R15") (pin "1") (pinfunction "1_1") (pintype "passive"))
    )
    (net (code "53") (name "Net-(LED5-PadA)") (class "Default")
      (node (ref "LED5") (pin "A") (pinfunction "A_A") (pintype "passive"))
      (node (ref "R16") (pin "1") (pinfunction "1_1") (pintype "passive"))
    )
    (net (code "54") (name "Net-(LED6-PadA)") (class "Default")
      (node (ref "LED6") (pin "A") (pinfunction "A_A") (pintype "passive"))
      (node (ref "R17") (pin "1") (pinfunction "1_1") (pintype "passive"))
    )
    (net (code "55") (name "Net-(LED7-PadA)") (class "Default")
      (node (ref "LED7") (pin "A") (pinfunction "A_A") (pintype "passive"))
      (node (ref "R18") (pin "1") (pinfunction "1_1") (pintype "passive"))
    )
    (net (code "56") (name "Net-(LED8-PadA)") (class "Default")
      (node (ref "LED8") (pin "A") (pinfunction "A_A") (pintype "passive"))
      (node (ref "R19") (pin "1") (pinfunction "1_1") (pintype "passive"))
    )
    (net (code "57") (name "Net-(LED9-PadA)") (class "Default")
      (node (ref "LED9") (pin "A") (pinfunction "A_A") (pintype "passive"))
      (node (ref "R20") (pin "1") (pinfunction "1_1") (pintype "passive"))
    )
    (net (code "58") (name "Net-(LED10-PadA)") (class "Default")
      (node (ref "LED10") (pin "A") (pinfunction "A_A") (pintype "passive"))
      (node (ref "R26") (pin "1") (pinfunction "1_1") (pintype "passive"))
    )
    (net (code "59") (name "Net-(LED11-PadA)") (class "Default")
      (node (ref "LED11") (pin "A") (pinfunction "A_A") (pintype "passive"))
      (node (ref "R29") (pin "1") (pinfunction "1_1") (pintype "passive"))
    )
    (net (code "60") (name "Net-(LED12-PadA)") (class "Default")
      (node (ref "LED12") (pin "A") (pinfunction "A_A") (pintype "passive"))
      (node (ref "R32") (pin "1") (pinfunction "1_1") (pintype "passive"))
    )
    (net (code "61") (name "Net-(LED13-PadA)") (class "Default")
      (node (ref "LED13") (pin "A") (pinfunction "A_A") (pintype "passive"))
      (node (ref "R35") (pin "1") (pinfunction "1_1") (pintype "passive"))
    )
    (net (code "62") (name "Net-(LED15-PadA)") (class "Default")
      (node (ref "LED15") (pin "A") (pinfunction "A_A") (pintype "passive"))
      (node (ref "R37") (pin "1") (pinfunction "1_1") (pintype "passive"))
    )
    (net (code "63") (name "Net-(LED16-PadA)") (class "Default")
      (node (ref "LED16") (pin "A") (pinfunction "A_A") (pintype "passive"))
      (node (ref "R38") (pin "1") (pinfunction "1_1") (pintype "passive"))
    )
    (net (code "64") (name "Net-(LED17-PadA)") (class "Default")
      (node (ref "LED17") (pin "A") (pinfunction "A_A") (pintype "passive"))
      (node (ref "R39") (pin "1") (pinfunction "1_1") (pintype "passive"))
    )
    (net (code "65") (name "Net-(LED18-PadA)") (class "Default")
      (node (ref "LED18") (pin "A") (pinfunction "A_A") (pintype "passive"))
      (node (ref "R40") (pin "1") (pinfunction "1_1") (pintype "passive"))
    )
    (net (code "66") (name "Net-(LED19-PadA)") (class "Default")
      (node (ref "LED19") (pin "A") (pinfunction "A_A") (pintype "passive"))
      (node (ref "R59") (pin "1") (pinfunction "1_1") (pintype "passive"))
    )
    (net (code "67") (name "Net-(LED20-PadA)") (class "Default")
      (node (ref "LED20") (pin "A") (pinfunction "A_A") (pintype "passive"))
      (node (ref "R60") (pin "1") (pinfunction "1_1") (pintype "passive"))
    )
    (net (code "68") (name "Net-(OK1-A)") (class "Default")
      (node (ref "OK1") (pin "1") (pinfunction "A_1") (pintype "passive"))
      (node (ref "R6") (pin "2") (pinfunction "2_2") (pintype "passive"))
    )
    (net (code "69") (name "Net-(OK1-C)") (class "Default")
      (node (ref "OK1") (pin "2") (pinfunction "C_2") (pintype "passive"))
      (node (ref "X1") (pin "2") (pinfunction "KL_2") (pintype "passive"))
    )
    (net (code "70") (name "Net-(OK2-A)") (class "Default")
      (node (ref "OK2") (pin "1") (pinfunction "A_1") (pintype "passive"))
      (node (ref "R5") (pin "2") (pinfunction "2_2") (pintype "passive"))
    )
    (net (code "71") (name "Net-(OK2-C)") (class "Default")
      (node (ref "OK2") (pin "2") (pinfunction "C_2") (pintype "passive"))
      (node (ref "X1") (pin "4") (pinfunction "KL_4") (pintype "passive"))
    )
    (net (code "72") (name "Net-(OK3-A)") (class "Default")
      (node (ref "OK3") (pin "1") (pinfunction "A_1") (pintype "passive"))
      (node (ref "R8") (pin "2") (pinfunction "2_2") (pintype "passive"))
    )
    (net (code "73") (name "Net-(OK3-C)") (class "Default")
      (node (ref "OK3") (pin "2") (pinfunction "C_2") (pintype "passive"))
      (node (ref "X1") (pin "6") (pinfunction "KL_6") (pintype "passive"))
    )
    (net (code "74") (name "Net-(OK4-A)") (class "Default")
      (node (ref "OK4") (pin "1") (pinfunction "A_1") (pintype "passive"))
      (node (ref "R9") (pin "2") (pinfunction "2_2") (pintype "passive"))
    )
    (net (code "75") (name "Net-(OK4-C)") (class "Default")
      (node (ref "OK4") (pin "2") (pinfunction "C_2") (pintype "passive"))
      (node (ref "X1") (pin "8") (pinfunction "KL_8") (pintype "passive"))
    )
    (net (code "76") (name "Net-(OK5-A)") (class "Default")
      (node (ref "OK5") (pin "1") (pinfunction "A_1") (pintype "passive"))
      (node (ref "R10") (pin "2") (pinfunction "2_2") (pintype "passive"))
    )
    (net (code "77") (name "Net-(OK5-C)") (class "Default")
      (node (ref "OK5") (pin "2") (pinfunction "C_2") (pintype "passive"))
      (node (ref "X2") (pin "2") (pinfunction "KL_2") (pintype "passive"))
    )
    (net (code "78") (name "Net-(OK6-A)") (class "Default")
      (node (ref "OK6") (pin "1") (pinfunction "A_1") (pintype "passive"))
      (node (ref "R11") (pin "2") (pinfunction "2_2") (pintype "passive"))
    )
    (net (code "79") (name "Net-(OK6-C)") (class "Default")
      (node (ref "OK6") (pin "2") (pinfunction "C_2") (pintype "passive"))
      (node (ref "X2") (pin "4") (pinfunction "KL_4") (pintype "passive"))
    )
    (net (code "80") (name "Net-(OK7-A)") (class "Default")
      (node (ref "OK7") (pin "1") (pinfunction "A_1") (pintype "passive"))
      (node (ref "R12") (pin "2") (pinfunction "2_2") (pintype "passive"))
    )
    (net (code "81") (name "Net-(OK7-C)") (class "Default")
      (node (ref "OK7") (pin "2") (pinfunction "C_2") (pintype "passive"))
      (node (ref "X2") (pin "6") (pinfunction "KL_6") (pintype "passive"))
    )
    (net (code "82") (name "Net-(OK8-A)") (class "Default")
      (node (ref "OK8") (pin "1") (pinfunction "A_1") (pintype "passive"))
      (node (ref "R13") (pin "2") (pinfunction "2_2") (pintype "passive"))
    )
    (net (code "83") (name "Net-(OK8-C)") (class "Default")
      (node (ref "OK8") (pin "2") (pinfunction "C_2") (pintype "passive"))
      (node (ref "X2") (pin "8") (pinfunction "KL_8") (pintype "passive"))
    )
    (net (code "84") (name "Net-(T1-B)") (class "Default")
      (node (ref "R42") (pin "1") (pinfunction "1_1") (pintype "passive"))
      (node (ref "T1") (pin "3") (pinfunction "B_3") (pintype "passive"))
    )
    (net (code "85") (name "Net-(T1-E)") (class "Default")
      (node (ref "LED16") (pin "C") (pinfunction "C_C") (pintype "passive"))
      (node (ref "T1") (pin "2") (pinfunction "E_2") (pintype "passive"))
    )
    (net (code "86") (name "Net-(T2-B)") (class "Default")
      (node (ref "R28") (pin "1") (pinfunction "1_1") (pintype "passive"))
      (node (ref "T2") (pin "3") (pinfunction "B_3") (pintype "passive"))
    )
    (net (code "87") (name "Net-(T2-E)") (class "Default")
      (node (ref "D3") (pin "A") (pinfunction "A_A") (pintype "passive"))
      (node (ref "K3") (pin "2") (pinfunction "2_2") (pintype "passive"))
      (node (ref "LED11") (pin "C") (pinfunction "C_C") (pintype "passive"))
      (node (ref "T2") (pin "2") (pinfunction "E_2") (pintype "passive"))
    )
    (net (code "88") (name "Net-(T3-B)") (class "Default")
      (node (ref "R43") (pin "1") (pinfunction "1_1") (pintype "passive"))
      (node (ref "T3") (pin "3") (pinfunction "B_3") (pintype "passive"))
    )
    (net (code "89") (name "Net-(T3-E)") (class "Default")
      (node (ref "LED17") (pin "C") (pinfunction "C_C") (pintype "passive"))
      (node (ref "T3") (pin "2") (pinfunction "E_2") (pintype "passive"))
    )
    (net (code "90") (name "Net-(T4-B)") (class "Default")
      (node (ref "R44") (pin "1") (pinfunction "1_1") (pintype "passive"))
      (node (ref "T4") (pin "3") (pinfunction "B_3") (pintype "passive"))
    )
    (net (code "91") (name "Net-(T4-E)") (class "Default")
      (node (ref "LED18") (pin "C") (pinfunction "C_C") (pintype "passive"))
      (node (ref "T4") (pin "2") (pinfunction "E_2") (pintype "passive"))
    )
    (net (code "92") (name "Net-(T5-B)") (class "Default")
      (node (ref "R33") (pin "1") (pinfunction "1_1") (pintype "passive"))
      (node (ref "R34") (pin "2") (pinfunction "2_2") (pintype "passive"))
      (node (ref "T5") (pin "3") (pinfunction "B_3") (pintype "passive"))
    )
    (net (code "93") (name "Net-(T5-C)") (class "Default")
      (node (ref "LED13") (pin "C") (pinfunction "C_C") (pintype "passive"))
      (node (ref "SG1") (pin "-") (pinfunction "-_-") (pintype "passive"))
      (node (ref "T5") (pin "1") (pinfunction "C_1") (pintype "passive"))
    )
    (net (code "94") (name "Net-(T6-B)") (class "Default")
      (node (ref "R31") (pin "1") (pinfunction "1_1") (pintype "passive"))
      (node (ref "T6") (pin "3") (pinfunction "B_3") (pintype "passive"))
    )
    (net (code "95") (name "Net-(T6-E)") (class "Default")
      (node (ref "D4") (pin "A") (pinfunction "A_A") (pintype "passive"))
      (node (ref "K4") (pin "2") (pinfunction "2_2") (pintype "passive"))
      (node (ref "LED12") (pin "C") (pinfunction "C_C") (pintype "passive"))
      (node (ref "T6") (pin "2") (pinfunction "E_2") (pintype "passive"))
    )
    (net (code "96") (name "Net-(T7-B)") (class "Default")
      (node (ref "R25") (pin "1") (pinfunction "1_1") (pintype "passive"))
      (node (ref "T7") (pin "3") (pinfunction "B_3") (pintype "passive"))
    )
    (net (code "97") (name "Net-(T7-E)") (class "Default")
      (node (ref "D2") (pin "A") (pinfunction "A_A") (pintype "passive"))
      (node (ref "K2") (pin "2") (pinfunction "2_2") (pintype "passive"))
      (node (ref "LED10") (pin "C") (pinfunction "C_C") (pintype "passive"))
      (node (ref "T7") (pin "2") (pinfunction "E_2") (pintype "passive"))
    )
    (net (code "98") (name "Net-(T8-B)") (class "Default")
      (node (ref "R22") (pin "1") (pinfunction "1_1") (pintype "passive"))
      (node (ref "T8") (pin "3") (pinfunction "B_3") (pintype "passive"))
    )
    (net (code "99") (name "Net-(T8-E)") (class "Default")
      (node (ref "D1") (pin "A") (pinfunction "A_A") (pintype "passive"))
      (node (ref "K1") (pin "2") (pinfunction "2_2") (pintype "passive"))
      (node (ref "LED1") (pin "C") (pinfunction "C_C") (pintype "passive"))
      (node (ref "T8") (pin "2") (pinfunction "E_2") (pintype "passive"))
    )
    (net (code "100") (name "Net-(T10-B)") (class "Default")
      (node (ref "R41") (pin "1") (pinfunction "1_1") (pintype "passive"))
      (node (ref "T10") (pin "3") (pinfunction "B_3") (pintype "passive"))
    )
    (net (code "101") (name "Net-(T10-E)") (class "Default")
      (node (ref "LED15") (pin "C") (pinfunction "C_C") (pintype "passive"))
      (node (ref "T10") (pin "2") (pinfunction "E_2") (pintype "passive"))
    )
    (net (code "102") (name "Net-(X1A-KL)") (class "Default")
      (node (ref "R6") (pin "1") (pinfunction "1_1") (pintype "passive"))
      (node (ref "X1") (pin "1") (pinfunction "KL_1") (pintype "passive"))
    )
    (net (code "103") (name "Net-(X1C-KL)") (class "Default")
      (node (ref "R5") (pin "1") (pinfunction "1_1") (pintype "passive"))
      (node (ref "X1") (pin "3") (pinfunction "KL_3") (pintype "passive"))
    )
    (net (code "104") (name "Net-(X1E-KL)") (class "Default")
      (node (ref "R8") (pin "1") (pinfunction "1_1") (pintype "passive"))
      (node (ref "X1") (pin "5") (pinfunction "KL_5") (pintype "passive"))
    )
    (net (code "105") (name "Net-(X1G-KL)") (class "Default")
      (node (ref "R9") (pin "1") (pinfunction "1_1") (pintype "passive"))
      (node (ref "X1") (pin "7") (pinfunction "KL_7") (pintype "passive"))
    )
    (net (code "106") (name "Net-(X2A-KL)") (class "Default")
      (node (ref "R10") (pin "1") (pinfunction "1_1") (pintype "passive"))
      (node (ref "X2") (pin "1") (pinfunction "KL_1") (pintype "passive"))
    )
    (net (code "107") (name "Net-(X2C-KL)") (class "Default")
      (node (ref "R11") (pin "1") (pinfunction "1_1") (pintype "passive"))
      (node (ref "X2") (pin "3") (pinfunction "KL_3") (pintype "passive"))
    )
    (net (code "108") (name "Net-(X2E-KL)") (class "Default")
      (node (ref "R12") (pin "1") (pinfunction "1_1") (pintype "passive"))
      (node (ref "X2") (pin "5") (pinfunction "KL_5") (pintype "passive"))
    )
    (net (code "109") (name "Net-(X2G-KL)") (class "Default")
      (node (ref "R13") (pin "1") (pinfunction "1_1") (pintype "passive"))
      (node (ref "X2") (pin "7") (pinfunction "KL_7") (pintype "passive"))
    )
    (net (code "110") (name "Net-(X3A-KL)") (class "Default")
      (node (ref "K1") (pin "C@1") (pinfunction "P_C@1") (pintype "passive"))
      (node (ref "X3") (pin "1") (pinfunction "KL_1") (pintype "passive"))
    )
    (net (code "111") (name "Net-(X4A-KL)") (class "Default")
      (node (ref "K2") (pin "C@1") (pinfunction "P_C@1") (pintype "passive"))
      (node (ref "X4") (pin "1") (pinfunction "KL_1") (pintype "passive"))
    )
    (net (code "112") (name "Net-(X5A-KL)") (class "Default")
      (node (ref "K3") (pin "C@1") (pinfunction "P_C@1") (pintype "passive"))
      (node (ref "X5") (pin "1") (pinfunction "KL_1") (pintype "passive"))
    )
    (net (code "113") (name "Net-(X6A-KL)") (class "Default")
      (node (ref "K4") (pin "C@1") (pinfunction "P_C@1") (pintype "passive"))
      (node (ref "X6") (pin "1") (pinfunction "KL_1") (pintype "passive"))
    )
    (net (code "114") (name "unconnected-(J2-Pad2)") (class "Default")
      (node (ref "J2") (pin "2") (pinfunction "2_2") (pintype "passive"))
    )
    (net (code "115") (name "unconnected-(K1B-P-PadC@2)") (class "Default")
      (node (ref "K1") (pin "C@2") (pinfunction "P_C@2") (pintype "passive"))
    )
    (net (code "116") (name "unconnected-(K2B-P-PadC@2)") (class "Default")
      (node (ref "K2") (pin "C@2") (pinfunction "P_C@2") (pintype "passive"))
    )
    (net (code "117") (name "unconnected-(K3B-P-PadC@2)") (class "Default")
      (node (ref "K3") (pin "C@2") (pinfunction "P_C@2") (pintype "passive"))
    )
    (net (code "118") (name "unconnected-(K4B-P-PadC@2)") (class "Default")
      (node (ref "K4") (pin "C@2") (pinfunction "P_C@2") (pintype "passive"))
    )
    (net (code "119") (name "unconnected-(S1-1.2-Pad2)") (class "Default")
      (node (ref "S1") (pin "2") (pinfunction "1.2_2") (pintype "passive"))
    )
    (net (code "120") (name "unconnected-(S1-2.2-Pad4)") (class "Default")
      (node (ref "S1") (pin "4") (pinfunction "2.2_4") (pintype "passive"))
    )
    (net (code "121") (name "unconnected-(S1-SH-Pad5)") (class "Default")
      (node (ref "S1") (pin "5") (pinfunction "SH_5") (pintype "passive"))
    )
    (net (code "122") (name "unconnected-(SV6-Pad1)") (class "Default")
      (node (ref "SV6") (pin "1") (pinfunction "1_1") (pintype "passive"))
    )
    (net (code "123") (name "unconnected-(SV6-Pad10)") (class "Default")
      (node (ref "SV6") (pin "10") (pinfunction "10_10") (pintype "passive"))
    )
    (net (code "124") (name "unconnected-(U$2-Pad0)") (class "Default")
      (node (ref "U$2") (pin "0") (pinfunction "0_0") (pintype "bidirectional"))
    )
    (net (code "125") (name "unconnected-(U$2-Pad4)") (class "Default")
      (node (ref "U$2") (pin "4") (pinfunction "4_4") (pintype "bidirectional"))
    )
    (net (code "126") (name "unconnected-(U$2-Pad13)") (class "Default")
      (node (ref "U$2") (pin "13") (pinfunction "13_13") (pintype "bidirectional"))
    )
    (net (code "127") (name "unconnected-(U$2-PadRST)") (class "Default")
      (node (ref "U$2") (pin "RST") (pinfunction "RST_RST") (pintype "bidirectional"))
    )
    (net (code "128") (name "unconnected-(U$2-PadRXD)") (class "Default")
      (node (ref "U$2") (pin "RXD") (pinfunction "RXD_RXD") (pintype "bidirectional"))
    )
    (net (code "129") (name "unconnected-(U$2-PadTXD)") (class "Default")
      (node (ref "U$2") (pin "TXD") (pinfunction "TXD_TXD") (pintype "bidirectional"))
    )
  )
)
